# E-scooter.net
KiCad netlist of a schematic drawn in Altium Designer
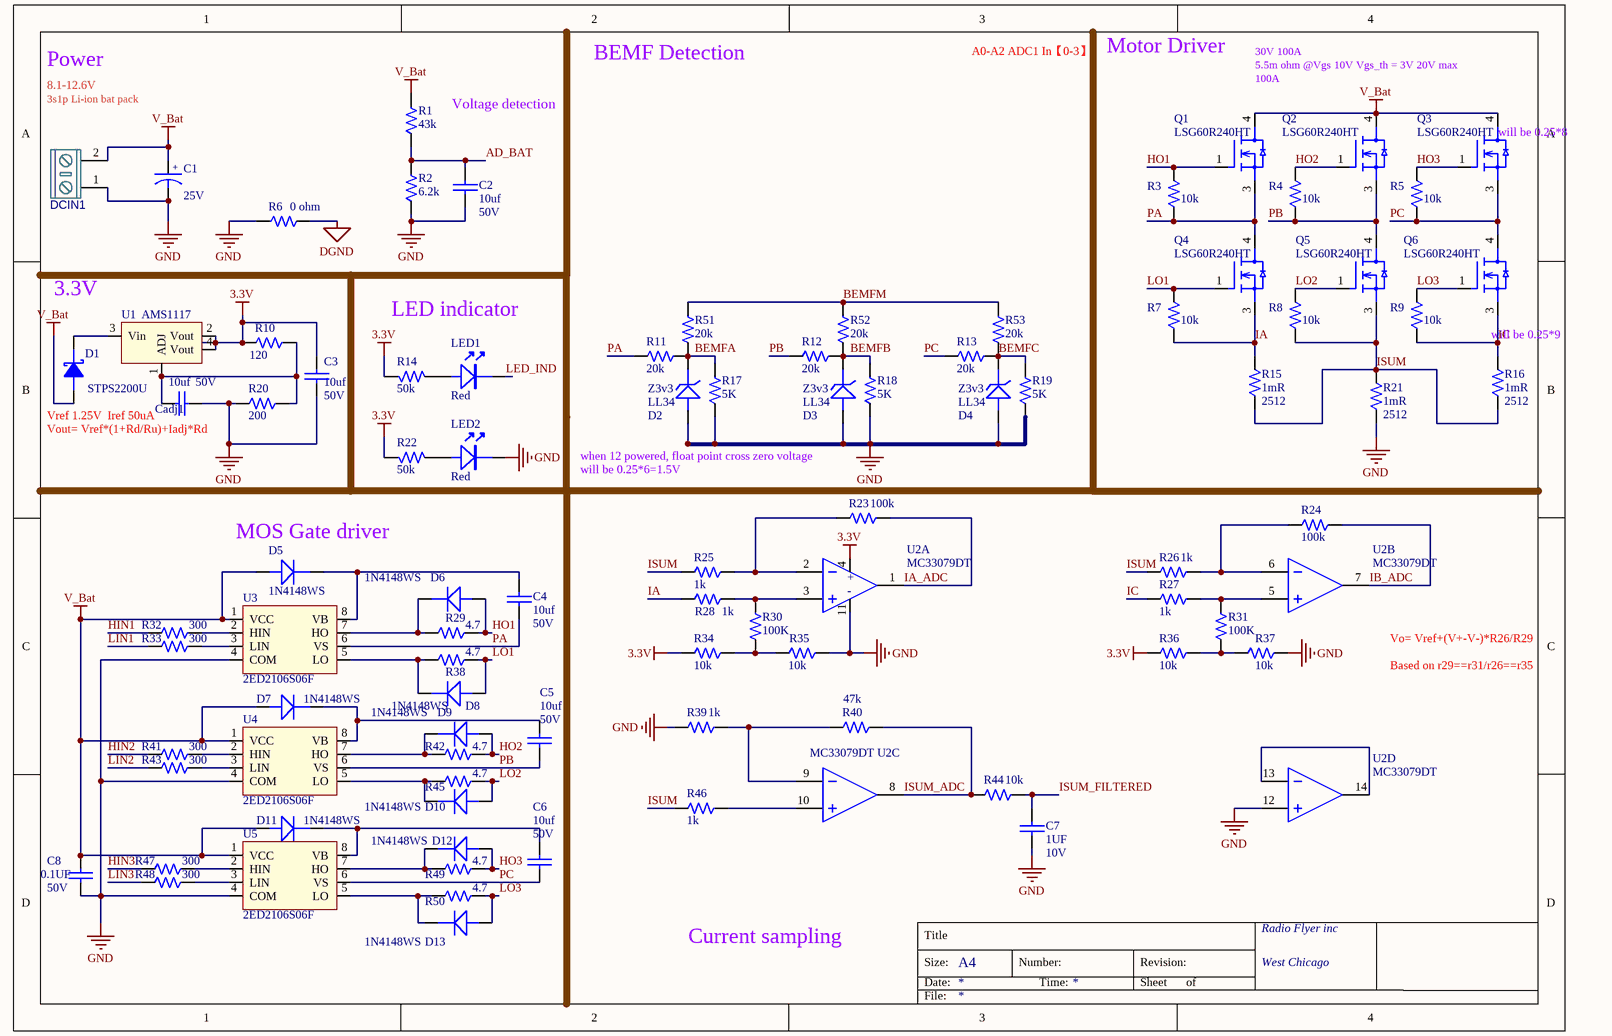
[diagram p0: E-scooter.SchDoc]

(export (version "E")
  (design (tool "Eeschema 10.0.6"))
  (components
    (comp (ref "C1")
      (value "PBE099550-4710")
      (footprint "CASE - G")
      (description "CHIP ELECT 470uF 25V 20% D10xL10 105")
      (fields (field (name "TOLERANCE") "20%") (field (name "VOLTAGE") "25V"))
      (libsource (lib "P-Capacitors") (part "CAP E 470uF 25V 20% SMD"))
    )
    (comp (ref "C2")
      (value "10uf")
      (footprint "CAPC0603-RW")
      (description "GP CHIP CAP 0.015uF 50V 10% 0603 TYPE X7R")
      (fields
        (field (name "TOLERANCE") "10%")
        (field (name "VOLTAGE") "50V")
        (field (name "Comment") "PXL456470-1530")
      )
      (libsource (lib "P-Capacitors") (part "CAP0603 0.015uF 50V 10%"))
    )
    (comp (ref "C3")
      (value "10uf")
      (footprint "CAPC0603-RW")
      (description "GP CHIP CAP 0.015uF 50V 10% 0603 TYPE X7R")
      (fields
        (field (name "TOLERANCE") "10%")
        (field (name "VOLTAGE") "50V")
        (field (name "Comment") "PXL456470-1530")
      )
      (libsource (lib "P-Capacitors") (part "CAP0603 0.015uF 50V 10%"))
    )
    (comp (ref "C4")
      (value "10uf")
      (footprint "CAPC0603-RW")
      (description "GP CHIP CAP 0.015uF 50V 10% 0603 TYPE X7R")
      (fields
        (field (name "TOLERANCE") "10%")
        (field (name "VOLTAGE") "50V")
        (field (name "Comment") "PXL456470-1530")
      )
      (libsource (lib "P-Capacitors") (part "CAP0603 0.015uF 50V 10%"))
    )
    (comp (ref "C5")
      (value "10uf")
      (footprint "CAPC0603-RW")
      (description "GP CHIP CAP 0.015uF 50V 10% 0603 TYPE X7R")
      (fields
        (field (name "TOLERANCE") "10%")
        (field (name "VOLTAGE") "50V")
        (field (name "Comment") "PXL456470-1530")
      )
      (libsource (lib "P-Capacitors") (part "CAP0603 0.015uF 50V 10%"))
    )
    (comp (ref "C6")
      (value "10uf")
      (footprint "CAPC0603-RW")
      (description "GP CHIP CAP 0.015uF 50V 10% 0603 TYPE X7R")
      (fields
        (field (name "TOLERANCE") "10%")
        (field (name "VOLTAGE") "50V")
        (field (name "Comment") "PXL456470-1530")
      )
      (libsource (lib "P-Capacitors") (part "CAP0603 0.015uF 50V 10%"))
    )
    (comp (ref "C7")
      (value "1UF")
      (footprint "CAPC0603-SW")
      (description "GP CHIP CAP 0.015uF 50V 10% 0603 TYPE X7R")
      (fields
        (field (name "TOLERANCE") "10%")
        (field (name "VOLTAGE") "10V")
        (field (name "Comment") "PXL456470-1530")
      )
      (libsource (lib "P-Capacitors") (part "CAP0603 0.015uF 50V 10%"))
    )
    (comp (ref "C8")
      (value "0.1UF")
      (footprint "CAPC0603-RW")
      (description "GP CHIP CAP 0.015uF 50V 10% 0603 TYPE X7R")
      (fields
        (field (name "TOLERANCE") "10%")
        (field (name "VOLTAGE") "50V")
        (field (name "Comment") "PXL456470-1530")
      )
      (libsource (lib "P-Capacitors") (part "CAP0603 0.015uF 50V 10%"))
    )
    (comp (ref "Cadj1")
      (value "10uf")
      (footprint "CAPC0603-RW")
      (description "GP CHIP CAP 0.015uF 50V 10% 0603 TYPE X7R")
      (fields
        (field (name "TOLERANCE") "10%")
        (field (name "VOLTAGE") "50V")
        (field (name "Comment") "PXL456470-1530")
      )
      (libsource (lib "P-Capacitors") (part "CAP0603 0.015uF 50V 10%"))
    )
    (comp (ref "D1")
      (value "DIO STPS2200U")
      (footprint "SMB")
      (description "DIODE SCHOTTKY 200V 2A SMB")
      (fields
        (field (name "MFG") "STMicroelectronics")
        (field (name "MFG PART") "STPS2200U")
        (field (name "CREATE_NAME") "Nathan")
      )
      (libsource (lib "R-Semiconductors") (part "DIO STPS2200U"))
    )
    (comp (ref "D2")
      (value "RCZ005015-0020")
      (footprint "LL34")
      (description "CHIP ZENER 15V 0.5W MLL34")
      (fields
        (field (name "MFG") "TAK CHEONG")
        (field (name "TOLERANCE") "5%")
        (field (name "MFG PART") "Z3v3")
        (field (name "PACKAGE") "LL34")
      )
      (libsource (lib "R-Semiconductors") (part "TCLLZ15V"))
    )
    (comp (ref "D3")
      (value "RCZ005015-0020")
      (footprint "LL34")
      (description "CHIP ZENER 15V 0.5W MLL34")
      (fields
        (field (name "MFG") "TAK CHEONG")
        (field (name "TOLERANCE") "5%")
        (field (name "MFG PART") "Z3v3")
        (field (name "PACKAGE") "LL34")
      )
      (libsource (lib "R-Semiconductors") (part "TCLLZ15V"))
    )
    (comp (ref "D4")
      (value "RCZ005015-0020")
      (footprint "LL34")
      (description "CHIP ZENER 15V 0.5W MLL34")
      (fields
        (field (name "MFG") "TAK CHEONG")
        (field (name "TOLERANCE") "5%")
        (field (name "MFG PART") "Z3v3")
        (field (name "PACKAGE") "LL34")
      )
      (libsource (lib "R-Semiconductors") (part "TCLLZ15V"))
    )
    (comp (ref "D5")
      (value "RCD114148-0020")
      (footprint "SOD-323")
      (description "DIODE SW 1N4148 VF=0.7V SOD-323")
      (fields
        (field (name "MFG") "TW SEMICONDUCTOR")
        (field (name "VOLTAGE") "100V")
        (field (name "MFG PART") "1N4148WS")
      )
      (libsource (lib "R-Semiconductors") (part "1N4148WS"))
    )
    (comp (ref "D6")
      (value "RCD114148-0020")
      (footprint "SOD-323")
      (description "DIODE SW 1N4148 VF=0.7V SOD-323")
      (fields
        (field (name "MFG") "TW SEMICONDUCTOR")
        (field (name "VOLTAGE") "100V")
        (field (name "MFG PART") "1N4148WS")
      )
      (libsource (lib "R-Semiconductors") (part "1N4148WS"))
    )
    (comp (ref "D7")
      (value "RCD114148-0020")
      (footprint "SOD-323")
      (description "DIODE SW 1N4148 VF=0.7V SOD-323")
      (fields
        (field (name "MFG") "TW SEMICONDUCTOR")
        (field (name "VOLTAGE") "100V")
        (field (name "MFG PART") "1N4148WS")
      )
      (libsource (lib "R-Semiconductors") (part "1N4148WS"))
    )
    (comp (ref "D8")
      (value "RCD114148-0020")
      (footprint "SOD-323")
      (description "DIODE SW 1N4148 VF=0.7V SOD-323")
      (fields
        (field (name "MFG") "TW SEMICONDUCTOR")
        (field (name "VOLTAGE") "100V")
        (field (name "MFG PART") "1N4148WS")
      )
      (libsource (lib "R-Semiconductors") (part "1N4148WS"))
    )
    (comp (ref "D9")
      (value "RCD114148-0020")
      (footprint "SOD-323")
      (description "DIODE SW 1N4148 VF=0.7V SOD-323")
      (fields
        (field (name "MFG") "TW SEMICONDUCTOR")
        (field (name "VOLTAGE") "100V")
        (field (name "MFG PART") "1N4148WS")
      )
      (libsource (lib "R-Semiconductors") (part "1N4148WS"))
    )
    (comp (ref "D10")
      (value "RCD114148-0020")
      (footprint "SOD-323")
      (description "DIODE SW 1N4148 VF=0.7V SOD-323")
      (fields
        (field (name "MFG") "TW SEMICONDUCTOR")
        (field (name "VOLTAGE") "100V")
        (field (name "MFG PART") "1N4148WS")
      )
      (libsource (lib "R-Semiconductors") (part "1N4148WS"))
    )
    (comp (ref "D11")
      (value "RCD114148-0020")
      (footprint "SOD-323")
      (description "DIODE SW 1N4148 VF=0.7V SOD-323")
      (fields
        (field (name "MFG") "TW SEMICONDUCTOR")
        (field (name "VOLTAGE") "100V")
        (field (name "MFG PART") "1N4148WS")
      )
      (libsource (lib "R-Semiconductors") (part "1N4148WS"))
    )
    (comp (ref "D12")
      (value "RCD114148-0020")
      (footprint "SOD-323")
      (description "DIODE SW 1N4148 VF=0.7V SOD-323")
      (fields
        (field (name "MFG") "TW SEMICONDUCTOR")
        (field (name "VOLTAGE") "100V")
        (field (name "MFG PART") "1N4148WS")
      )
      (libsource (lib "R-Semiconductors") (part "1N4148WS"))
    )
    (comp (ref "D13")
      (value "RCD114148-0020")
      (footprint "SOD-323")
      (description "DIODE SW 1N4148 VF=0.7V SOD-323")
      (fields
        (field (name "MFG") "TW SEMICONDUCTOR")
        (field (name "VOLTAGE") "100V")
        (field (name "MFG PART") "1N4148WS")
      )
      (libsource (lib "R-Semiconductors") (part "1N4148WS"))
    )
    (comp (ref "DCIN1")
      (value "KF/WJ/DG 30x connecter")
      (footprint "KF/WJ/DG 301-2p-5.0mm")
      (description "接线端子 2Pin")
      (libsource (lib "灵动SPIN360C 无刷驱动V1.6 集成封装库") (part "KF/WJ/DG 30x"))
    )
    (comp (ref "LED1")
      (value "LED1206R_23-2~{1}R6C-AM1N2A~{Y}2A")
      (footprint "LED1206-RED")
      (description "CHIP LED RED TYPE 1206")
      (fields
        (field (name "MFG PART") "23-2~{1}R6C-AM1N2A~{Y}2A")
        (field (name "MFG") "EVERLIGHT")
        (field (name "COLOR") "Red")
        (field (name "CREATE_NAME") "Nathan")
      )
      (libsource (lib "K-LED-FUSE") (part "LED1206R_23-21{backslash}R6C-AM1N2AY{backslash}2A"))
    )
    (comp (ref "LED2")
      (value "LED1206R_23-2~{1}R6C-AM1N2A~{Y}2A")
      (footprint "LED1206-RED")
      (description "CHIP LED RED TYPE 1206")
      (fields
        (field (name "MFG PART") "23-2~{1}R6C-AM1N2A~{Y}2A")
        (field (name "MFG") "EVERLIGHT")
        (field (name "COLOR") "Red")
        (field (name "CREATE_NAME") "Nathan")
      )
      (libsource (lib "K-LED-FUSE") (part "LED1206R_23-21{backslash}R6C-AM1N2AY{backslash}2A"))
    )
    (comp (ref "Q1")
      (value "T5860038503A6")
      (footprint "TO252-3")
      (description "NMOS 600V LSG60R240HT TO252( LONTEN K")
      (fields
        (field (name "VOLTAGE") "600V")
        (field (name "MFG") "LONTEN")
        (field (name "MFG PART") "LSG60R240HT")
        (field (name "CREATE_NAME") "Nathan")
      )
      (libsource (lib "R-Semiconductors") (part "NMOS LSG60R240HT"))
    )
    (comp (ref "Q2")
      (value "T5860038503A6")
      (footprint "TO252-3")
      (description "NMOS 600V LSG60R240HT TO252( LONTEN K")
      (fields
        (field (name "VOLTAGE") "600V")
        (field (name "MFG") "LONTEN")
        (field (name "MFG PART") "LSG60R240HT")
        (field (name "CREATE_NAME") "Nathan")
      )
      (libsource (lib "R-Semiconductors") (part "NMOS LSG60R240HT"))
    )
    (comp (ref "Q3")
      (value "T5860038503A6")
      (footprint "TO252-3")
      (description "NMOS 600V LSG60R240HT TO252( LONTEN K")
      (fields
        (field (name "VOLTAGE") "600V")
        (field (name "MFG") "LONTEN")
        (field (name "MFG PART") "LSG60R240HT")
        (field (name "CREATE_NAME") "Nathan")
      )
      (libsource (lib "R-Semiconductors") (part "NMOS LSG60R240HT"))
    )
    (comp (ref "Q4")
      (value "T5860038503A6")
      (footprint "TO252-3")
      (description "NMOS 600V LSG60R240HT TO252( LONTEN K")
      (fields
        (field (name "VOLTAGE") "600V")
        (field (name "MFG") "LONTEN")
        (field (name "MFG PART") "LSG60R240HT")
        (field (name "CREATE_NAME") "Nathan")
      )
      (libsource (lib "R-Semiconductors") (part "NMOS LSG60R240HT"))
    )
    (comp (ref "Q5")
      (value "T5860038503A6")
      (footprint "TO252-3")
      (description "NMOS 600V LSG60R240HT TO252( LONTEN K")
      (fields
        (field (name "VOLTAGE") "600V")
        (field (name "MFG") "LONTEN")
        (field (name "MFG PART") "LSG60R240HT")
        (field (name "CREATE_NAME") "Nathan")
      )
      (libsource (lib "R-Semiconductors") (part "NMOS LSG60R240HT"))
    )
    (comp (ref "Q6")
      (value "T5860038503A6")
      (footprint "TO252-3")
      (description "NMOS 600V LSG60R240HT TO252( LONTEN K")
      (fields
        (field (name "VOLTAGE") "600V")
        (field (name "MFG") "LONTEN")
        (field (name "MFG PART") "LSG60R240HT")
        (field (name "CREATE_NAME") "Nathan")
      )
      (libsource (lib "R-Semiconductors") (part "NMOS LSG60R240HT"))
    )
    (comp (ref "R1")
      (value "43k")
      (footprint "0603-RW")
      (description "CHIP 4.42K OHM 200PPM +-1% 0201 WALS L")
      (fields
        (field (name "POWER") "1/20W")
        (field (name "MFG PART") "WR02X4421FAL")
        (field (name "CREATE_NAME") "Nathan")
      )
      (libsource (lib "Q-Resistors") (part "RES0201 1/20W 1% 4.42K OHM_WALSIN"))
    )
    (comp (ref "R2")
      (value "6.2k")
      (footprint "0603-RW")
      (description "CHIP 4.42K OHM 200PPM +-1% 0201 WALS L")
      (fields
        (field (name "POWER") "1/20W")
        (field (name "MFG PART") "WR02X4421FAL")
        (field (name "CREATE_NAME") "Nathan")
      )
      (libsource (lib "Q-Resistors") (part "RES0201 1/20W 1% 4.42K OHM_WALSIN"))
    )
    (comp (ref "R3")
      (value "10k")
      (footprint "0603-RW")
      (description "CHIP 4.42K OHM 200PPM +-1% 0201 WALS L")
      (fields
        (field (name "POWER") "1/20W")
        (field (name "MFG PART") "WR02X4421FAL")
        (field (name "CREATE_NAME") "Nathan")
      )
      (libsource (lib "Q-Resistors") (part "RES0201 1/20W 1% 4.42K OHM_WALSIN"))
    )
    (comp (ref "R4")
      (value "10k")
      (footprint "0603-RW")
      (description "CHIP 4.42K OHM 200PPM +-1% 0201 WALS L")
      (fields
        (field (name "POWER") "1/20W")
        (field (name "MFG PART") "WR02X4421FAL")
        (field (name "CREATE_NAME") "Nathan")
      )
      (libsource (lib "Q-Resistors") (part "RES0201 1/20W 1% 4.42K OHM_WALSIN"))
    )
    (comp (ref "R5")
      (value "10k")
      (footprint "0603-RW")
      (description "CHIP 4.42K OHM 200PPM +-1% 0201 WALS L")
      (fields
        (field (name "POWER") "1/20W")
        (field (name "MFG PART") "WR02X4421FAL")
        (field (name "CREATE_NAME") "Nathan")
      )
      (libsource (lib "Q-Resistors") (part "RES0201 1/20W 1% 4.42K OHM_WALSIN"))
    )
    (comp (ref "R6")
      (value "0 ohm")
      (footprint "0603-RW")
      (description "CHIP 21K OHM 100PPM +-1% 0603 WALS L")
      (fields
        (field (name "MFG") "WALSIN (華新)")
        (field (name "POWER") "1/10W")
        (field (name "CREATE_NAME") "Nathan")
      )
      (libsource (lib "Q-Resistors") (part "RES0603 1/16W 1% 21K OMH_WALSIN"))
    )
    (comp (ref "R7")
      (value "10k")
      (footprint "0603-RW")
      (description "CHIP 4.42K OHM 200PPM +-1% 0201 WALS L")
      (fields
        (field (name "POWER") "1/20W")
        (field (name "MFG PART") "WR02X4421FAL")
        (field (name "CREATE_NAME") "Nathan")
      )
      (libsource (lib "Q-Resistors") (part "RES0201 1/20W 1% 4.42K OHM_WALSIN"))
    )
    (comp (ref "R8")
      (value "10k")
      (footprint "0603-RW")
      (description "CHIP 4.42K OHM 200PPM +-1% 0201 WALS L")
      (fields
        (field (name "POWER") "1/20W")
        (field (name "MFG PART") "WR02X4421FAL")
        (field (name "CREATE_NAME") "Nathan")
      )
      (libsource (lib "Q-Resistors") (part "RES0201 1/20W 1% 4.42K OHM_WALSIN"))
    )
    (comp (ref "R9")
      (value "10k")
      (footprint "0603-RW")
      (description "CHIP 4.42K OHM 200PPM +-1% 0201 WALS L")
      (fields
        (field (name "POWER") "1/20W")
        (field (name "MFG PART") "WR02X4421FAL")
        (field (name "CREATE_NAME") "Nathan")
      )
      (libsource (lib "Q-Resistors") (part "RES0201 1/20W 1% 4.42K OHM_WALSIN"))
    )
    (comp (ref "R10")
      (value "120")
      (footprint "0603-RW")
      (description "CHIP 4.42K OHM 200PPM +-1% 0201 WALS L")
      (fields
        (field (name "POWER") "1/20W")
        (field (name "MFG PART") "WR02X4421FAL")
        (field (name "CREATE_NAME") "Nathan")
      )
      (libsource (lib "Q-Resistors") (part "RES0201 1/20W 1% 4.42K OHM_WALSIN"))
    )
    (comp (ref "R11")
      (value "20k")
      (footprint "0603-RW")
      (description "CHIP 4.42K OHM 200PPM +-1% 0201 WALS L")
      (fields
        (field (name "POWER") "1/20W")
        (field (name "MFG PART") "WR02X4421FAL")
        (field (name "CREATE_NAME") "Nathan")
      )
      (libsource (lib "Q-Resistors") (part "RES0201 1/20W 1% 4.42K OHM_WALSIN"))
    )
    (comp (ref "R12")
      (value "20k")
      (footprint "0603-RW")
      (description "CHIP 4.42K OHM 200PPM +-1% 0201 WALS L")
      (fields
        (field (name "POWER") "1/20W")
        (field (name "MFG PART") "WR02X4421FAL")
        (field (name "CREATE_NAME") "Nathan")
      )
      (libsource (lib "Q-Resistors") (part "RES0201 1/20W 1% 4.42K OHM_WALSIN"))
    )
    (comp (ref "R13")
      (value "20k")
      (footprint "0603-RW")
      (description "CHIP 4.42K OHM 200PPM +-1% 0201 WALS L")
      (fields
        (field (name "POWER") "1/20W")
        (field (name "MFG PART") "WR02X4421FAL")
        (field (name "CREATE_NAME") "Nathan")
      )
      (libsource (lib "Q-Resistors") (part "RES0201 1/20W 1% 4.42K OHM_WALSIN"))
    )
    (comp (ref "R14")
      (value "50k")
      (footprint "0603-RW")
      (description "CHIP 4.42K OHM 200PPM +-1% 0201 WALS L")
      (fields
        (field (name "POWER") "1/20W")
        (field (name "MFG PART") "WR02X4421FAL")
        (field (name "CREATE_NAME") "Nathan")
      )
      (libsource (lib "Q-Resistors") (part "RES0201 1/20W 1% 4.42K OHM_WALSIN"))
    )
    (comp (ref "R15")
      (value "1mR")
      (footprint "2512")
      (description "CHIP RES. 10 OHM 1W 1% 2512")
      (fields
        (field (name "POWER") "1W")
        (field (name "PACKAGE") "2512")
        (field (name "Comment") "QCF101250-1009")
      )
      (libsource (lib "Q-Resistors") (part "RES2512 1W 1% 10 OHM"))
    )
    (comp (ref "R16")
      (value "1mR")
      (footprint "2512")
      (description "CHIP RES. 10 OHM 1W 1% 2512")
      (fields
        (field (name "POWER") "1W")
        (field (name "PACKAGE") "2512")
        (field (name "Comment") "QCF101250-1009")
      )
      (libsource (lib "Q-Resistors") (part "RES2512 1W 1% 10 OHM"))
    )
    (comp (ref "R17")
      (value "5K")
      (footprint "0603-RW")
      (description "CHIP 4.42K OHM 200PPM +-1% 0201 WALS L")
      (fields
        (field (name "POWER") "1/20W")
        (field (name "MFG PART") "WR02X4421FAL")
        (field (name "CREATE_NAME") "Nathan")
      )
      (libsource (lib "Q-Resistors") (part "RES0201 1/20W 1% 4.42K OHM_WALSIN"))
    )
    (comp (ref "R18")
      (value "5K")
      (footprint "0603-RW")
      (description "CHIP 4.42K OHM 200PPM +-1% 0201 WALS L")
      (fields
        (field (name "POWER") "1/20W")
        (field (name "MFG PART") "WR02X4421FAL")
        (field (name "CREATE_NAME") "Nathan")
      )
      (libsource (lib "Q-Resistors") (part "RES0201 1/20W 1% 4.42K OHM_WALSIN"))
    )
    (comp (ref "R19")
      (value "5K")
      (footprint "0603-RW")
      (description "CHIP 4.42K OHM 200PPM +-1% 0201 WALS L")
      (fields
        (field (name "POWER") "1/20W")
        (field (name "MFG PART") "WR02X4421FAL")
        (field (name "CREATE_NAME") "Nathan")
      )
      (libsource (lib "Q-Resistors") (part "RES0201 1/20W 1% 4.42K OHM_WALSIN"))
    )
    (comp (ref "R20")
      (value "200")
      (footprint "0603-RW")
      (description "CHIP 4.42K OHM 200PPM +-1% 0201 WALS L")
      (fields
        (field (name "POWER") "1/20W")
        (field (name "MFG PART") "WR02X4421FAL")
        (field (name "CREATE_NAME") "Nathan")
      )
      (libsource (lib "Q-Resistors") (part "RES0201 1/20W 1% 4.42K OHM_WALSIN"))
    )
    (comp (ref "R21")
      (value "1mR")
      (footprint "2512")
      (description "CHIP RES. 10 OHM 1W 1% 2512")
      (fields
        (field (name "POWER") "1W")
        (field (name "PACKAGE") "2512")
        (field (name "Comment") "QCF101250-1009")
      )
      (libsource (lib "Q-Resistors") (part "RES2512 1W 1% 10 OHM"))
    )
    (comp (ref "R22")
      (value "50k")
      (footprint "0603-RW")
      (description "CHIP 4.42K OHM 200PPM +-1% 0201 WALS L")
      (fields
        (field (name "POWER") "1/20W")
        (field (name "MFG PART") "WR02X4421FAL")
        (field (name "CREATE_NAME") "Nathan")
      )
      (libsource (lib "Q-Resistors") (part "RES0201 1/20W 1% 4.42K OHM_WALSIN"))
    )
    (comp (ref "R23")
      (value "100k")
      (footprint "0603-RW")
      (description "CHIP 4.42K OHM 200PPM +-1% 0201 WALS L")
      (fields
        (field (name "POWER") "1/20W")
        (field (name "MFG PART") "WR02X4421FAL")
        (field (name "CREATE_NAME") "Nathan")
      )
      (libsource (lib "Q-Resistors") (part "RES0201 1/20W 1% 4.42K OHM_WALSIN"))
    )
    (comp (ref "R24")
      (value "100k")
      (footprint "0603-RW")
      (description "CHIP 4.42K OHM 200PPM +-1% 0201 WALS L")
      (fields
        (field (name "POWER") "1/20W")
        (field (name "MFG PART") "WR02X4421FAL")
        (field (name "CREATE_NAME") "Nathan")
      )
      (libsource (lib "Q-Resistors") (part "RES0201 1/20W 1% 4.42K OHM_WALSIN"))
    )
    (comp (ref "R25")
      (value "1k")
      (footprint "0603-RW")
      (description "CHIP 4.42K OHM 200PPM +-1% 0201 WALS L")
      (fields
        (field (name "POWER") "1/20W")
        (field (name "MFG PART") "WR02X4421FAL")
        (field (name "CREATE_NAME") "Nathan")
      )
      (libsource (lib "Q-Resistors") (part "RES0201 1/20W 1% 4.42K OHM_WALSIN"))
    )
    (comp (ref "R26")
      (value "1k")
      (footprint "0603-RW")
      (description "CHIP 4.42K OHM 200PPM +-1% 0201 WALS L")
      (fields
        (field (name "POWER") "1/20W")
        (field (name "MFG PART") "WR02X4421FAL")
        (field (name "CREATE_NAME") "Nathan")
      )
      (libsource (lib "Q-Resistors") (part "RES0201 1/20W 1% 4.42K OHM_WALSIN"))
    )
    (comp (ref "R27")
      (value "1k")
      (footprint "0603-RW")
      (description "CHIP 4.42K OHM 200PPM +-1% 0201 WALS L")
      (fields
        (field (name "POWER") "1/20W")
        (field (name "MFG PART") "WR02X4421FAL")
        (field (name "CREATE_NAME") "Nathan")
      )
      (libsource (lib "Q-Resistors") (part "RES0201 1/20W 1% 4.42K OHM_WALSIN"))
    )
    (comp (ref "R28")
      (value "1k")
      (footprint "0603-RW")
      (description "CHIP 4.42K OHM 200PPM +-1% 0201 WALS L")
      (fields
        (field (name "POWER") "1/20W")
        (field (name "MFG PART") "WR02X4421FAL")
        (field (name "CREATE_NAME") "Nathan")
      )
      (libsource (lib "Q-Resistors") (part "RES0201 1/20W 1% 4.42K OHM_WALSIN"))
    )
    (comp (ref "R29")
      (value "4.7")
      (footprint "0603-RW")
      (description "CHIP 4.42K OHM 200PPM +-1% 0201 WALS L")
      (fields
        (field (name "POWER") "1/20W")
        (field (name "MFG PART") "WR02X4421FAL")
        (field (name "CREATE_NAME") "Nathan")
      )
      (libsource (lib "Q-Resistors") (part "RES0201 1/20W 1% 4.42K OHM_WALSIN"))
    )
    (comp (ref "R30")
      (value "100K")
      (footprint "0603-RW")
      (description "CHIP 4.42K OHM 200PPM +-1% 0201 WALS L")
      (fields
        (field (name "POWER") "1/20W")
        (field (name "MFG PART") "WR02X4421FAL")
        (field (name "CREATE_NAME") "Nathan")
      )
      (libsource (lib "Q-Resistors") (part "RES0201 1/20W 1% 4.42K OHM_WALSIN"))
    )
    (comp (ref "R31")
      (value "100K")
      (footprint "0603-RW")
      (description "CHIP 4.42K OHM 200PPM +-1% 0201 WALS L")
      (fields
        (field (name "POWER") "1/20W")
        (field (name "MFG PART") "WR02X4421FAL")
        (field (name "CREATE_NAME") "Nathan")
      )
      (libsource (lib "Q-Resistors") (part "RES0201 1/20W 1% 4.42K OHM_WALSIN"))
    )
    (comp (ref "R32")
      (value "300")
      (footprint "0603-RW")
      (description "CHIP 4.42K OHM 200PPM +-1% 0201 WALS L")
      (fields
        (field (name "POWER") "1/20W")
        (field (name "MFG PART") "WR02X4421FAL")
        (field (name "CREATE_NAME") "Nathan")
      )
      (libsource (lib "Q-Resistors") (part "RES0201 1/20W 1% 4.42K OHM_WALSIN"))
    )
    (comp (ref "R33")
      (value "300")
      (footprint "0603-RW")
      (description "CHIP 4.42K OHM 200PPM +-1% 0201 WALS L")
      (fields
        (field (name "POWER") "1/20W")
        (field (name "MFG PART") "WR02X4421FAL")
        (field (name "CREATE_NAME") "Nathan")
      )
      (libsource (lib "Q-Resistors") (part "RES0201 1/20W 1% 4.42K OHM_WALSIN"))
    )
    (comp (ref "R34")
      (value "10k")
      (footprint "0603-RW")
      (description "CHIP 4.42K OHM 200PPM +-1% 0201 WALS L")
      (fields
        (field (name "POWER") "1/20W")
        (field (name "MFG PART") "WR02X4421FAL")
        (field (name "CREATE_NAME") "Nathan")
      )
      (libsource (lib "Q-Resistors") (part "RES0201 1/20W 1% 4.42K OHM_WALSIN"))
    )
    (comp (ref "R35")
      (value "10k")
      (footprint "0603-RW")
      (description "CHIP 4.42K OHM 200PPM +-1% 0201 WALS L")
      (fields
        (field (name "POWER") "1/20W")
        (field (name "MFG PART") "WR02X4421FAL")
        (field (name "CREATE_NAME") "Nathan")
      )
      (libsource (lib "Q-Resistors") (part "RES0201 1/20W 1% 4.42K OHM_WALSIN"))
    )
    (comp (ref "R36")
      (value "10k")
      (footprint "0603-RW")
      (description "CHIP 4.42K OHM 200PPM +-1% 0201 WALS L")
      (fields
        (field (name "POWER") "1/20W")
        (field (name "MFG PART") "WR02X4421FAL")
        (field (name "CREATE_NAME") "Nathan")
      )
      (libsource (lib "Q-Resistors") (part "RES0201 1/20W 1% 4.42K OHM_WALSIN"))
    )
    (comp (ref "R37")
      (value "10k")
      (footprint "0603-RW")
      (description "CHIP 4.42K OHM 200PPM +-1% 0201 WALS L")
      (fields
        (field (name "POWER") "1/20W")
        (field (name "MFG PART") "WR02X4421FAL")
        (field (name "CREATE_NAME") "Nathan")
      )
      (libsource (lib "Q-Resistors") (part "RES0201 1/20W 1% 4.42K OHM_WALSIN"))
    )
    (comp (ref "R38")
      (value "4.7")
      (footprint "0603-RW")
      (description "CHIP 4.42K OHM 200PPM +-1% 0201 WALS L")
      (fields
        (field (name "POWER") "1/20W")
        (field (name "MFG PART") "WR02X4421FAL")
        (field (name "CREATE_NAME") "Nathan")
      )
      (libsource (lib "Q-Resistors") (part "RES0201 1/20W 1% 4.42K OHM_WALSIN"))
    )
    (comp (ref "R39")
      (value "1k")
      (footprint "0603-RW")
      (description "CHIP 4.42K OHM 200PPM +-1% 0201 WALS L")
      (fields
        (field (name "POWER") "1/20W")
        (field (name "MFG PART") "WR02X4421FAL")
        (field (name "CREATE_NAME") "Nathan")
      )
      (libsource (lib "Q-Resistors") (part "RES0201 1/20W 1% 4.42K OHM_WALSIN"))
    )
    (comp (ref "R40")
      (value "47k")
      (footprint "0603-RW")
      (description "CHIP 4.42K OHM 200PPM +-1% 0201 WALS L")
      (fields
        (field (name "POWER") "1/20W")
        (field (name "MFG PART") "WR02X4421FAL")
        (field (name "CREATE_NAME") "Nathan")
      )
      (libsource (lib "Q-Resistors") (part "RES0201 1/20W 1% 4.42K OHM_WALSIN"))
    )
    (comp (ref "R41")
      (value "300")
      (footprint "0603-RW")
      (description "CHIP 4.42K OHM 200PPM +-1% 0201 WALS L")
      (fields
        (field (name "POWER") "1/20W")
        (field (name "MFG PART") "WR02X4421FAL")
        (field (name "CREATE_NAME") "Nathan")
      )
      (libsource (lib "Q-Resistors") (part "RES0201 1/20W 1% 4.42K OHM_WALSIN"))
    )
    (comp (ref "R42")
      (value "4.7")
      (footprint "0603-RW")
      (description "CHIP 4.42K OHM 200PPM +-1% 0201 WALS L")
      (fields
        (field (name "POWER") "1/20W")
        (field (name "MFG PART") "WR02X4421FAL")
        (field (name "CREATE_NAME") "Nathan")
      )
      (libsource (lib "Q-Resistors") (part "RES0201 1/20W 1% 4.42K OHM_WALSIN"))
    )
    (comp (ref "R43")
      (value "300")
      (footprint "0603-RW")
      (description "CHIP 4.42K OHM 200PPM +-1% 0201 WALS L")
      (fields
        (field (name "POWER") "1/20W")
        (field (name "MFG PART") "WR02X4421FAL")
        (field (name "CREATE_NAME") "Nathan")
      )
      (libsource (lib "Q-Resistors") (part "RES0201 1/20W 1% 4.42K OHM_WALSIN"))
    )
    (comp (ref "R44")
      (value "10k")
      (footprint "0603-RW")
      (description "CHIP 4.42K OHM 200PPM +-1% 0201 WALS L")
      (fields
        (field (name "POWER") "1/20W")
        (field (name "MFG PART") "WR02X4421FAL")
        (field (name "CREATE_NAME") "Nathan")
      )
      (libsource (lib "Q-Resistors") (part "RES0201 1/20W 1% 4.42K OHM_WALSIN"))
    )
    (comp (ref "R45")
      (value "4.7")
      (footprint "0603-RW")
      (description "CHIP 4.42K OHM 200PPM +-1% 0201 WALS L")
      (fields
        (field (name "POWER") "1/20W")
        (field (name "MFG PART") "WR02X4421FAL")
        (field (name "CREATE_NAME") "Nathan")
      )
      (libsource (lib "Q-Resistors") (part "RES0201 1/20W 1% 4.42K OHM_WALSIN"))
    )
    (comp (ref "R46")
      (value "1k")
      (footprint "0603-RW")
      (description "CHIP 4.42K OHM 200PPM +-1% 0201 WALS L")
      (fields
        (field (name "POWER") "1/20W")
        (field (name "MFG PART") "WR02X4421FAL")
        (field (name "CREATE_NAME") "Nathan")
      )
      (libsource (lib "Q-Resistors") (part "RES0201 1/20W 1% 4.42K OHM_WALSIN"))
    )
    (comp (ref "R47")
      (value "300")
      (footprint "0603-RW")
      (description "CHIP 4.42K OHM 200PPM +-1% 0201 WALS L")
      (fields
        (field (name "POWER") "1/20W")
        (field (name "MFG PART") "WR02X4421FAL")
        (field (name "CREATE_NAME") "Nathan")
      )
      (libsource (lib "Q-Resistors") (part "RES0201 1/20W 1% 4.42K OHM_WALSIN"))
    )
    (comp (ref "R48")
      (value "300")
      (footprint "0603-RW")
      (description "CHIP 4.42K OHM 200PPM +-1% 0201 WALS L")
      (fields
        (field (name "POWER") "1/20W")
        (field (name "MFG PART") "WR02X4421FAL")
        (field (name "CREATE_NAME") "Nathan")
      )
      (libsource (lib "Q-Resistors") (part "RES0201 1/20W 1% 4.42K OHM_WALSIN"))
    )
    (comp (ref "R49")
      (value "4.7")
      (footprint "0603-RW")
      (description "CHIP 4.42K OHM 200PPM +-1% 0201 WALS L")
      (fields
        (field (name "POWER") "1/20W")
        (field (name "MFG PART") "WR02X4421FAL")
        (field (name "CREATE_NAME") "Nathan")
      )
      (libsource (lib "Q-Resistors") (part "RES0201 1/20W 1% 4.42K OHM_WALSIN"))
    )
    (comp (ref "R50")
      (value "4.7")
      (footprint "0603-RW")
      (description "CHIP 4.42K OHM 200PPM +-1% 0201 WALS L")
      (fields
        (field (name "POWER") "1/20W")
        (field (name "MFG PART") "WR02X4421FAL")
        (field (name "CREATE_NAME") "Nathan")
      )
      (libsource (lib "Q-Resistors") (part "RES0201 1/20W 1% 4.42K OHM_WALSIN"))
    )
    (comp (ref "R51")
      (value "20k")
      (footprint "0603-RW")
      (description "CHIP 4.42K OHM 200PPM +-1% 0201 WALS L")
      (fields
        (field (name "POWER") "1/20W")
        (field (name "MFG PART") "WR02X4421FAL")
        (field (name "CREATE_NAME") "Nathan")
      )
      (libsource (lib "Q-Resistors") (part "RES0201 1/20W 1% 4.42K OHM_WALSIN"))
    )
    (comp (ref "R52")
      (value "20k")
      (footprint "0603-RW")
      (description "CHIP 4.42K OHM 200PPM +-1% 0201 WALS L")
      (fields
        (field (name "POWER") "1/20W")
        (field (name "MFG PART") "WR02X4421FAL")
        (field (name "CREATE_NAME") "Nathan")
      )
      (libsource (lib "Q-Resistors") (part "RES0201 1/20W 1% 4.42K OHM_WALSIN"))
    )
    (comp (ref "R53")
      (value "20k")
      (footprint "0603-RW")
      (description "CHIP 4.42K OHM 200PPM +-1% 0201 WALS L")
      (fields
        (field (name "POWER") "1/20W")
        (field (name "MFG PART") "WR02X4421FAL")
        (field (name "CREATE_NAME") "Nathan")
      )
      (libsource (lib "Q-Resistors") (part "RES0201 1/20W 1% 4.42K OHM_WALSIN"))
    )
    (comp (ref "U1")
      (value "AMS1117")
      (footprint "SOT223")
      (description "800mA LOW DROPOUT VOLTAGE REGULATOR , SOT-223")
      (fields
        (field (name "MFG") "Advanced Monolithic Systems")
        (field (name "MFG PART") "AMS1117")
        (field (name "CREATE_NAME") "Nathan")
      )
      (libsource (lib "R-Semiconductors") (part "AMS1117"))
    )
    (comp (ref "U2")
      (value "RCI033079-0002")
      (footprint "SO14")
      (description "IC opamp quad MC33079 bipolar SO14")
      (fields (field (name "MFG") "STMICROELECTRONICS") (field (name "MFG PART") "MC33079DT"))
      (libsource (lib "R-Semiconductors") (part "MC33079DT"))
    )
    (comp (ref "U3")
      (value "T610900027257")
      (footprint "SO8")
      (description "DRIVER 2ED2106S06F DSO-8 INFINEO K")
      (fields
        (field (name "MFG") "Infineon")
        (field (name "MFG PART") "2ED2106S06F")
        (field (name "CREATE_NAME") "Nathan")
      )
      (libsource (lib "R-Semiconductors") (part "2ED2106S06F"))
    )
    (comp (ref "U4")
      (value "T610900027257")
      (footprint "SO8")
      (description "DRIVER 2ED2106S06F DSO-8 INFINEO K")
      (fields
        (field (name "MFG") "Infineon")
        (field (name "MFG PART") "2ED2106S06F")
        (field (name "CREATE_NAME") "Nathan")
      )
      (libsource (lib "R-Semiconductors") (part "2ED2106S06F"))
    )
    (comp (ref "U5")
      (value "T610900027257")
      (footprint "SO8")
      (description "DRIVER 2ED2106S06F DSO-8 INFINEO K")
      (fields
        (field (name "MFG") "Infineon")
        (field (name "MFG PART") "2ED2106S06F")
        (field (name "CREATE_NAME") "Nathan")
      )
      (libsource (lib "R-Semiconductors") (part "2ED2106S06F"))
    )
  )
  (nets
    (net (code "1") (name "/AD_BAT") (class "Default")
      (node (ref "C2") (pin "1") (pinfunction "1_1") (pintype "passive"))
      (node (ref "R1") (pin "2") (pinfunction "2_2") (pintype "passive"))
      (node (ref "R2") (pin "1") (pinfunction "1_1") (pintype "passive"))
    )
    (net (code "2") (name "/BEMFA") (class "Default")
      (node (ref "D2") (pin "2") (pinfunction "K_2") (pintype "passive"))
      (node (ref "R11") (pin "1") (pinfunction "1_1") (pintype "passive"))
      (node (ref "R17") (pin "1") (pinfunction "1_1") (pintype "passive"))
      (node (ref "R51") (pin "2") (pinfunction "2_2") (pintype "passive"))
    )
    (net (code "3") (name "/BEMFB") (class "Default")
      (node (ref "D3") (pin "2") (pinfunction "K_2") (pintype "passive"))
      (node (ref "R12") (pin "1") (pinfunction "1_1") (pintype "passive"))
      (node (ref "R18") (pin "1") (pinfunction "1_1") (pintype "passive"))
      (node (ref "R52") (pin "2") (pinfunction "2_2") (pintype "passive"))
    )
    (net (code "4") (name "/BEMFC") (class "Default")
      (node (ref "D4") (pin "2") (pinfunction "K_2") (pintype "passive"))
      (node (ref "R13") (pin "1") (pinfunction "1_1") (pintype "passive"))
      (node (ref "R19") (pin "1") (pinfunction "1_1") (pintype "passive"))
      (node (ref "R53") (pin "2") (pinfunction "2_2") (pintype "passive"))
    )
    (net (code "5") (name "/BEMFM") (class "Default")
      (node (ref "R51") (pin "1") (pinfunction "1_1") (pintype "passive"))
      (node (ref "R52") (pin "1") (pinfunction "1_1") (pintype "passive"))
      (node (ref "R53") (pin "1") (pinfunction "1_1") (pintype "passive"))
    )
    (net (code "6") (name "/HIN1") (class "Default")
      (node (ref "R32") (pin "2") (pinfunction "2_2") (pintype "passive"))
    )
    (net (code "7") (name "/HIN2") (class "Default")
      (node (ref "R41") (pin "2") (pinfunction "2_2") (pintype "passive"))
    )
    (net (code "8") (name "/HIN3") (class "Default")
      (node (ref "R47") (pin "2") (pinfunction "2_2") (pintype "passive"))
    )
    (net (code "9") (name "/HO1") (class "Default")
      (node (ref "D6") (pin "1") (pinfunction "A_1") (pintype "passive"))
      (node (ref "Q1") (pin "1") (pinfunction "G_1") (pintype "passive"))
      (node (ref "R29") (pin "1") (pinfunction "1_1") (pintype "passive"))
      (node (ref "R3") (pin "2") (pinfunction "2_2") (pintype "passive"))
    )
    (net (code "10") (name "/HO2") (class "Default")
      (node (ref "D9") (pin "1") (pinfunction "A_1") (pintype "passive"))
      (node (ref "Q2") (pin "1") (pinfunction "G_1") (pintype "passive"))
      (node (ref "R4") (pin "2") (pinfunction "2_2") (pintype "passive"))
      (node (ref "R42") (pin "1") (pinfunction "1_1") (pintype "passive"))
    )
    (net (code "11") (name "/HO3") (class "Default")
      (node (ref "D12") (pin "1") (pinfunction "A_1") (pintype "passive"))
      (node (ref "Q3") (pin "1") (pinfunction "G_1") (pintype "passive"))
      (node (ref "R49") (pin "1") (pinfunction "1_1") (pintype "passive"))
      (node (ref "R5") (pin "2") (pinfunction "2_2") (pintype "passive"))
    )
    (net (code "12") (name "/IA") (class "Default")
      (node (ref "Q4") (pin "3") (pinfunction "S_3") (pintype "passive"))
      (node (ref "R15") (pin "2") (pinfunction "2_2") (pintype "passive"))
      (node (ref "R28") (pin "2") (pinfunction "2_2") (pintype "passive"))
      (node (ref "R7") (pin "1") (pinfunction "1_1") (pintype "passive"))
    )
    (net (code "13") (name "/IA_ADC") (class "Default")
      (node (ref "R23") (pin "1") (pinfunction "1_1") (pintype "passive"))
      (node (ref "U2") (pin "1") (pinfunction "OUT_1") (pintype "passive"))
    )
    (net (code "14") (name "/IB_ADC") (class "Default")
      (node (ref "R24") (pin "1") (pinfunction "1_1") (pintype "passive"))
      (node (ref "U2") (pin "7") (pinfunction "OUT_7") (pintype "passive"))
    )
    (net (code "15") (name "/IC") (class "Default")
      (node (ref "Q6") (pin "3") (pinfunction "S_3") (pintype "passive"))
      (node (ref "R16") (pin "2") (pinfunction "2_2") (pintype "passive"))
      (node (ref "R27") (pin "2") (pinfunction "2_2") (pintype "passive"))
      (node (ref "R9") (pin "1") (pinfunction "1_1") (pintype "passive"))
    )
    (net (code "16") (name "/ISUM") (class "Default")
      (node (ref "Q5") (pin "3") (pinfunction "S_3") (pintype "passive"))
      (node (ref "R15") (pin "1") (pinfunction "1_1") (pintype "passive"))
      (node (ref "R16") (pin "1") (pinfunction "1_1") (pintype "passive"))
      (node (ref "R21") (pin "2") (pinfunction "2_2") (pintype "passive"))
      (node (ref "R25") (pin "2") (pinfunction "2_2") (pintype "passive"))
      (node (ref "R26") (pin "2") (pinfunction "2_2") (pintype "passive"))
      (node (ref "R46") (pin "2") (pinfunction "2_2") (pintype "passive"))
      (node (ref "R8") (pin "1") (pinfunction "1_1") (pintype "passive"))
    )
    (net (code "17") (name "/ISUM_ADC") (class "Default")
      (node (ref "R40") (pin "1") (pinfunction "1_1") (pintype "passive"))
      (node (ref "R44") (pin "2") (pinfunction "2_2") (pintype "passive"))
      (node (ref "U2") (pin "8") (pinfunction "OUT_8") (pintype "passive"))
    )
    (net (code "18") (name "/ISUM_FILTERED") (class "Default")
      (node (ref "C7") (pin "2") (pinfunction "2_2") (pintype "passive"))
      (node (ref "R44") (pin "1") (pinfunction "1_1") (pintype "passive"))
    )
    (net (code "19") (name "/LED_IND") (class "Default")
      (node (ref "LED1") (pin "2") (pinfunction "K_2") (pintype "passive"))
    )
    (net (code "20") (name "/LIN1") (class "Default")
      (node (ref "R33") (pin "2") (pinfunction "2_2") (pintype "passive"))
    )
    (net (code "21") (name "/LIN2") (class "Default")
      (node (ref "R43") (pin "2") (pinfunction "2_2") (pintype "passive"))
    )
    (net (code "22") (name "/LIN3") (class "Default")
      (node (ref "R48") (pin "2") (pinfunction "2_2") (pintype "passive"))
    )
    (net (code "23") (name "/LO1") (class "Default")
      (node (ref "D8") (pin "1") (pinfunction "A_1") (pintype "passive"))
      (node (ref "Q4") (pin "1") (pinfunction "G_1") (pintype "passive"))
      (node (ref "R38") (pin "1") (pinfunction "1_1") (pintype "passive"))
      (node (ref "R7") (pin "2") (pinfunction "2_2") (pintype "passive"))
    )
    (net (code "24") (name "/LO2") (class "Default")
      (node (ref "D10") (pin "1") (pinfunction "A_1") (pintype "passive"))
      (node (ref "Q5") (pin "1") (pinfunction "G_1") (pintype "passive"))
      (node (ref "R45") (pin "1") (pinfunction "1_1") (pintype "passive"))
      (node (ref "R8") (pin "2") (pinfunction "2_2") (pintype "passive"))
    )
    (net (code "25") (name "/LO3") (class "Default")
      (node (ref "D13") (pin "1") (pinfunction "A_1") (pintype "passive"))
      (node (ref "Q6") (pin "1") (pinfunction "G_1") (pintype "passive"))
      (node (ref "R50") (pin "1") (pinfunction "1_1") (pintype "passive"))
      (node (ref "R9") (pin "2") (pinfunction "2_2") (pintype "passive"))
    )
    (net (code "26") (name "/PA") (class "Default")
      (node (ref "C4") (pin "1") (pinfunction "1_1") (pintype "passive"))
      (node (ref "Q1") (pin "3") (pinfunction "S_3") (pintype "passive"))
      (node (ref "Q4") (pin "4") (pinfunction "D_4") (pintype "passive"))
      (node (ref "R11") (pin "2") (pinfunction "2_2") (pintype "passive"))
      (node (ref "R3") (pin "1") (pinfunction "1_1") (pintype "passive"))
      (node (ref "U3") (pin "6") (pinfunction "VS_6") (pintype "passive"))
    )
    (net (code "27") (name "/PB") (class "Default")
      (node (ref "C5") (pin "1") (pinfunction "1_1") (pintype "passive"))
      (node (ref "Q2") (pin "3") (pinfunction "S_3") (pintype "passive"))
      (node (ref "Q5") (pin "4") (pinfunction "D_4") (pintype "passive"))
      (node (ref "R12") (pin "2") (pinfunction "2_2") (pintype "passive"))
      (node (ref "R4") (pin "1") (pinfunction "1_1") (pintype "passive"))
      (node (ref "U4") (pin "6") (pinfunction "VS_6") (pintype "passive"))
    )
    (net (code "28") (name "/PC") (class "Default")
      (node (ref "C6") (pin "1") (pinfunction "1_1") (pintype "passive"))
      (node (ref "Q3") (pin "3") (pinfunction "S_3") (pintype "passive"))
      (node (ref "Q6") (pin "4") (pinfunction "D_4") (pintype "passive"))
      (node (ref "R13") (pin "2") (pinfunction "2_2") (pintype "passive"))
      (node (ref "R5") (pin "1") (pinfunction "1_1") (pintype "passive"))
      (node (ref "U5") (pin "6") (pinfunction "VS_6") (pintype "passive"))
    )
    (net (code "29") (name "3.3V") (class "Default")
      (node (ref "C3") (pin "1") (pinfunction "1_1") (pintype "passive"))
      (node (ref "R10") (pin "2") (pinfunction "2_2") (pintype "passive"))
      (node (ref "R14") (pin "1") (pinfunction "1_1") (pintype "passive"))
      (node (ref "R22") (pin "1") (pinfunction "1_1") (pintype "passive"))
      (node (ref "R34") (pin "2") (pinfunction "2_2") (pintype "passive"))
      (node (ref "R36") (pin "2") (pinfunction "2_2") (pintype "passive"))
      (node (ref "U1") (pin "2") (pinfunction "Vout_2") (pintype "passive"))
      (node (ref "U1") (pin "4") (pinfunction "Vout_4") (pintype "passive"))
      (node (ref "U2") (pin "4") (pinfunction "+V_4") (pintype "passive"))
    )
    (net (code "30") (name "DGND") (class "Default")
      (node (ref "R6") (pin "2") (pinfunction "2_2") (pintype "passive"))
    )
    (net (code "31") (name "GND") (class "Default")
      (node (ref "C1") (pin "2") (pinfunction "2_2") (pintype "passive"))
      (node (ref "C2") (pin "2") (pinfunction "2_2") (pintype "passive"))
      (node (ref "C3") (pin "2") (pinfunction "2_2") (pintype "passive"))
      (node (ref "C7") (pin "1") (pinfunction "1_1") (pintype "passive"))
      (node (ref "C8") (pin "1") (pinfunction "1_1") (pintype "passive"))
      (node (ref "Cadj1") (pin "2") (pinfunction "2_2") (pintype "passive"))
      (node (ref "D2") (pin "1") (pinfunction "A_1") (pintype "passive"))
      (node (ref "D3") (pin "1") (pinfunction "A_1") (pintype "passive"))
      (node (ref "D4") (pin "1") (pinfunction "A_1") (pintype "passive"))
      (node (ref "DCIN1") (pin "1") (pinfunction "1_1") (pintype "passive"))
      (node (ref "LED2") (pin "2") (pinfunction "K_2") (pintype "passive"))
      (node (ref "R17") (pin "2") (pinfunction "2_2") (pintype "passive"))
      (node (ref "R18") (pin "2") (pinfunction "2_2") (pintype "passive"))
      (node (ref "R19") (pin "2") (pinfunction "2_2") (pintype "passive"))
      (node (ref "R2") (pin "2") (pinfunction "2_2") (pintype "passive"))
      (node (ref "R20") (pin "2") (pinfunction "2_2") (pintype "passive"))
      (node (ref "R21") (pin "1") (pinfunction "1_1") (pintype "passive"))
      (node (ref "R35") (pin "1") (pinfunction "1_1") (pintype "passive"))
      (node (ref "R37") (pin "1") (pinfunction "1_1") (pintype "passive"))
      (node (ref "R39") (pin "2") (pinfunction "2_2") (pintype "passive"))
      (node (ref "R6") (pin "1") (pinfunction "1_1") (pintype "passive"))
      (node (ref "U2") (pin "11") (pinfunction "-V_11") (pintype "passive"))
      (node (ref "U2") (pin "12") (pinfunction "IN+_12") (pintype "passive"))
      (node (ref "U3") (pin "4") (pinfunction "COM_4") (pintype "passive"))
      (node (ref "U4") (pin "4") (pinfunction "COM_4") (pintype "passive"))
      (node (ref "U5") (pin "4") (pinfunction "COM_4") (pintype "passive"))
    )
    (net (code "32") (name "Net-(D1-K)") (class "Default")
      (node (ref "D1") (pin "2") (pinfunction "K_2") (pintype "passive"))
      (node (ref "U1") (pin "3") (pinfunction "Vin_3") (pintype "passive"))
    )
    (net (code "33") (name "Net-(D5-K)") (class "Default")
      (node (ref "C4") (pin "2") (pinfunction "2_2") (pintype "passive"))
      (node (ref "D5") (pin "2") (pinfunction "K_2") (pintype "passive"))
      (node (ref "U3") (pin "8") (pinfunction "VB_8") (pintype "passive"))
    )
    (net (code "34") (name "Net-(D6-K)") (class "Default")
      (node (ref "D6") (pin "2") (pinfunction "K_2") (pintype "passive"))
      (node (ref "R29") (pin "2") (pinfunction "2_2") (pintype "passive"))
      (node (ref "U3") (pin "7") (pinfunction "HO_7") (pintype "passive"))
    )
    (net (code "35") (name "Net-(D7-K)") (class "Default")
      (node (ref "C5") (pin "2") (pinfunction "2_2") (pintype "passive"))
      (node (ref "D7") (pin "2") (pinfunction "K_2") (pintype "passive"))
      (node (ref "U4") (pin "8") (pinfunction "VB_8") (pintype "passive"))
    )
    (net (code "36") (name "Net-(D8-K)") (class "Default")
      (node (ref "D8") (pin "2") (pinfunction "K_2") (pintype "passive"))
      (node (ref "R38") (pin "2") (pinfunction "2_2") (pintype "passive"))
      (node (ref "U3") (pin "5") (pinfunction "LO_5") (pintype "passive"))
    )
    (net (code "37") (name "Net-(D9-K)") (class "Default")
      (node (ref "D9") (pin "2") (pinfunction "K_2") (pintype "passive"))
      (node (ref "R42") (pin "2") (pinfunction "2_2") (pintype "passive"))
      (node (ref "U4") (pin "7") (pinfunction "HO_7") (pintype "passive"))
    )
    (net (code "38") (name "Net-(D10-K)") (class "Default")
      (node (ref "D10") (pin "2") (pinfunction "K_2") (pintype "passive"))
      (node (ref "R45") (pin "2") (pinfunction "2_2") (pintype "passive"))
      (node (ref "U4") (pin "5") (pinfunction "LO_5") (pintype "passive"))
    )
    (net (code "39") (name "Net-(D11-K)") (class "Default")
      (node (ref "C6") (pin "2") (pinfunction "2_2") (pintype "passive"))
      (node (ref "D11") (pin "2") (pinfunction "K_2") (pintype "passive"))
      (node (ref "U5") (pin "8") (pinfunction "VB_8") (pintype "passive"))
    )
    (net (code "40") (name "Net-(D12-K)") (class "Default")
      (node (ref "D12") (pin "2") (pinfunction "K_2") (pintype "passive"))
      (node (ref "R49") (pin "2") (pinfunction "2_2") (pintype "passive"))
      (node (ref "U5") (pin "7") (pinfunction "HO_7") (pintype "passive"))
    )
    (net (code "41") (name "Net-(D13-K)") (class "Default")
      (node (ref "D13") (pin "2") (pinfunction "K_2") (pintype "passive"))
      (node (ref "R50") (pin "2") (pinfunction "2_2") (pintype "passive"))
      (node (ref "U5") (pin "5") (pinfunction "LO_5") (pintype "passive"))
    )
    (net (code "42") (name "Net-(LED1-A)") (class "Default")
      (node (ref "LED1") (pin "1") (pinfunction "A_1") (pintype "passive"))
      (node (ref "R14") (pin "2") (pinfunction "2_2") (pintype "passive"))
    )
    (net (code "43") (name "Net-(LED2-A)") (class "Default")
      (node (ref "LED2") (pin "1") (pinfunction "A_1") (pintype "passive"))
      (node (ref "R22") (pin "2") (pinfunction "2_2") (pintype "passive"))
    )
    (net (code "44") (name "Net-(R30-Pad2)") (class "Default")
      (node (ref "R30") (pin "2") (pinfunction "2_2") (pintype "passive"))
      (node (ref "R34") (pin "1") (pinfunction "1_1") (pintype "passive"))
      (node (ref "R35") (pin "2") (pinfunction "2_2") (pintype "passive"))
    )
    (net (code "45") (name "Net-(R31-Pad2)") (class "Default")
      (node (ref "R31") (pin "2") (pinfunction "2_2") (pintype "passive"))
      (node (ref "R36") (pin "1") (pinfunction "1_1") (pintype "passive"))
      (node (ref "R37") (pin "2") (pinfunction "2_2") (pintype "passive"))
    )
    (net (code "46") (name "Net-(U1-ADJ)") (class "Default")
      (node (ref "Cadj1") (pin "1") (pinfunction "1_1") (pintype "passive"))
      (node (ref "R10") (pin "1") (pinfunction "1_1") (pintype "passive"))
      (node (ref "R20") (pin "1") (pinfunction "1_1") (pintype "passive"))
      (node (ref "U1") (pin "1") (pinfunction "ADJ_1") (pintype "passive"))
    )
    (net (code "47") (name "Net-(U2A-IN+)") (class "Default")
      (node (ref "R28") (pin "1") (pinfunction "1_1") (pintype "passive"))
      (node (ref "R30") (pin "1") (pinfunction "1_1") (pintype "passive"))
      (node (ref "U2") (pin "3") (pinfunction "IN+_3") (pintype "passive"))
    )
    (net (code "48") (name "Net-(U2A-IN-)") (class "Default")
      (node (ref "R23") (pin "2") (pinfunction "2_2") (pintype "passive"))
      (node (ref "R25") (pin "1") (pinfunction "1_1") (pintype "passive"))
      (node (ref "U2") (pin "2") (pinfunction "IN-_2") (pintype "passive"))
    )
    (net (code "49") (name "Net-(U2B-IN+)") (class "Default")
      (node (ref "R27") (pin "1") (pinfunction "1_1") (pintype "passive"))
      (node (ref "R31") (pin "1") (pinfunction "1_1") (pintype "passive"))
      (node (ref "U2") (pin "5") (pinfunction "IN+_5") (pintype "passive"))
    )
    (net (code "50") (name "Net-(U2B-IN-)") (class "Default")
      (node (ref "R24") (pin "2") (pinfunction "2_2") (pintype "passive"))
      (node (ref "R26") (pin "1") (pinfunction "1_1") (pintype "passive"))
      (node (ref "U2") (pin "6") (pinfunction "IN-_6") (pintype "passive"))
    )
    (net (code "51") (name "Net-(U2C-IN+)") (class "Default")
      (node (ref "R46") (pin "1") (pinfunction "1_1") (pintype "passive"))
      (node (ref "U2") (pin "10") (pinfunction "IN+_10") (pintype "passive"))
    )
    (net (code "52") (name "Net-(U2C-IN-)") (class "Default")
      (node (ref "R39") (pin "1") (pinfunction "1_1") (pintype "passive"))
      (node (ref "R40") (pin "2") (pinfunction "2_2") (pintype "passive"))
      (node (ref "U2") (pin "9") (pinfunction "IN-_9") (pintype "passive"))
    )
    (net (code "53") (name "Net-(U2D-IN-)") (class "Default")
      (node (ref "U2") (pin "13") (pinfunction "IN-_13") (pintype "passive"))
      (node (ref "U2") (pin "14") (pinfunction "OUT_14") (pintype "passive"))
    )
    (net (code "54") (name "Net-(U3-HIN)") (class "Default")
      (node (ref "R32") (pin "1") (pinfunction "1_1") (pintype "passive"))
      (node (ref "U3") (pin "2") (pinfunction "HIN_2") (pintype "passive"))
    )
    (net (code "55") (name "Net-(U3-LIN)") (class "Default")
      (node (ref "R33") (pin "1") (pinfunction "1_1") (pintype "passive"))
      (node (ref "U3") (pin "3") (pinfunction "LIN_3") (pintype "passive"))
    )
    (net (code "56") (name "Net-(U4-HIN)") (class "Default")
      (node (ref "R41") (pin "1") (pinfunction "1_1") (pintype "passive"))
      (node (ref "U4") (pin "2") (pinfunction "HIN_2") (pintype "passive"))
    )
    (net (code "57") (name "Net-(U4-LIN)") (class "Default")
      (node (ref "R43") (pin "1") (pinfunction "1_1") (pintype "passive"))
      (node (ref "U4") (pin "3") (pinfunction "LIN_3") (pintype "passive"))
    )
    (net (code "58") (name "Net-(U5-HIN)") (class "Default")
      (node (ref "R47") (pin "1") (pinfunction "1_1") (pintype "passive"))
      (node (ref "U5") (pin "2") (pinfunction "HIN_2") (pintype "passive"))
    )
    (net (code "59") (name "Net-(U5-LIN)") (class "Default")
      (node (ref "R48") (pin "1") (pinfunction "1_1") (pintype "passive"))
      (node (ref "U5") (pin "3") (pinfunction "LIN_3") (pintype "passive"))
    )
    (net (code "60") (name "V_Bat") (class "Default")
      (node (ref "C1") (pin "1") (pinfunction "1_1") (pintype "passive"))
      (node (ref "C8") (pin "2") (pinfunction "2_2") (pintype "passive"))
      (node (ref "D1") (pin "1") (pinfunction "A_1") (pintype "passive"))
      (node (ref "D11") (pin "1") (pinfunction "A_1") (pintype "passive"))
      (node (ref "D5") (pin "1") (pinfunction "A_1") (pintype "passive"))
      (node (ref "D7") (pin "1") (pinfunction "A_1") (pintype "passive"))
      (node (ref "DCIN1") (pin "2") (pinfunction "2_2") (pintype "passive"))
      (node (ref "Q1") (pin "4") (pinfunction "D_4") (pintype "passive"))
      (node (ref "Q2") (pin "4") (pinfunction "D_4") (pintype "passive"))
      (node (ref "Q3") (pin "4") (pinfunction "D_4") (pintype "passive"))
      (node (ref "R1") (pin "1") (pinfunction "1_1") (pintype "passive"))
      (node (ref "U3") (pin "1") (pinfunction "VCC_1") (pintype "passive"))
      (node (ref "U4") (pin "1") (pinfunction "VCC_1") (pintype "passive"))
      (node (ref "U5") (pin "1") (pinfunction "VCC_1") (pintype "passive"))
    )
  )
)
